# Domino_LED.net
KiCad netlist of a schematic drawn in EAGLE
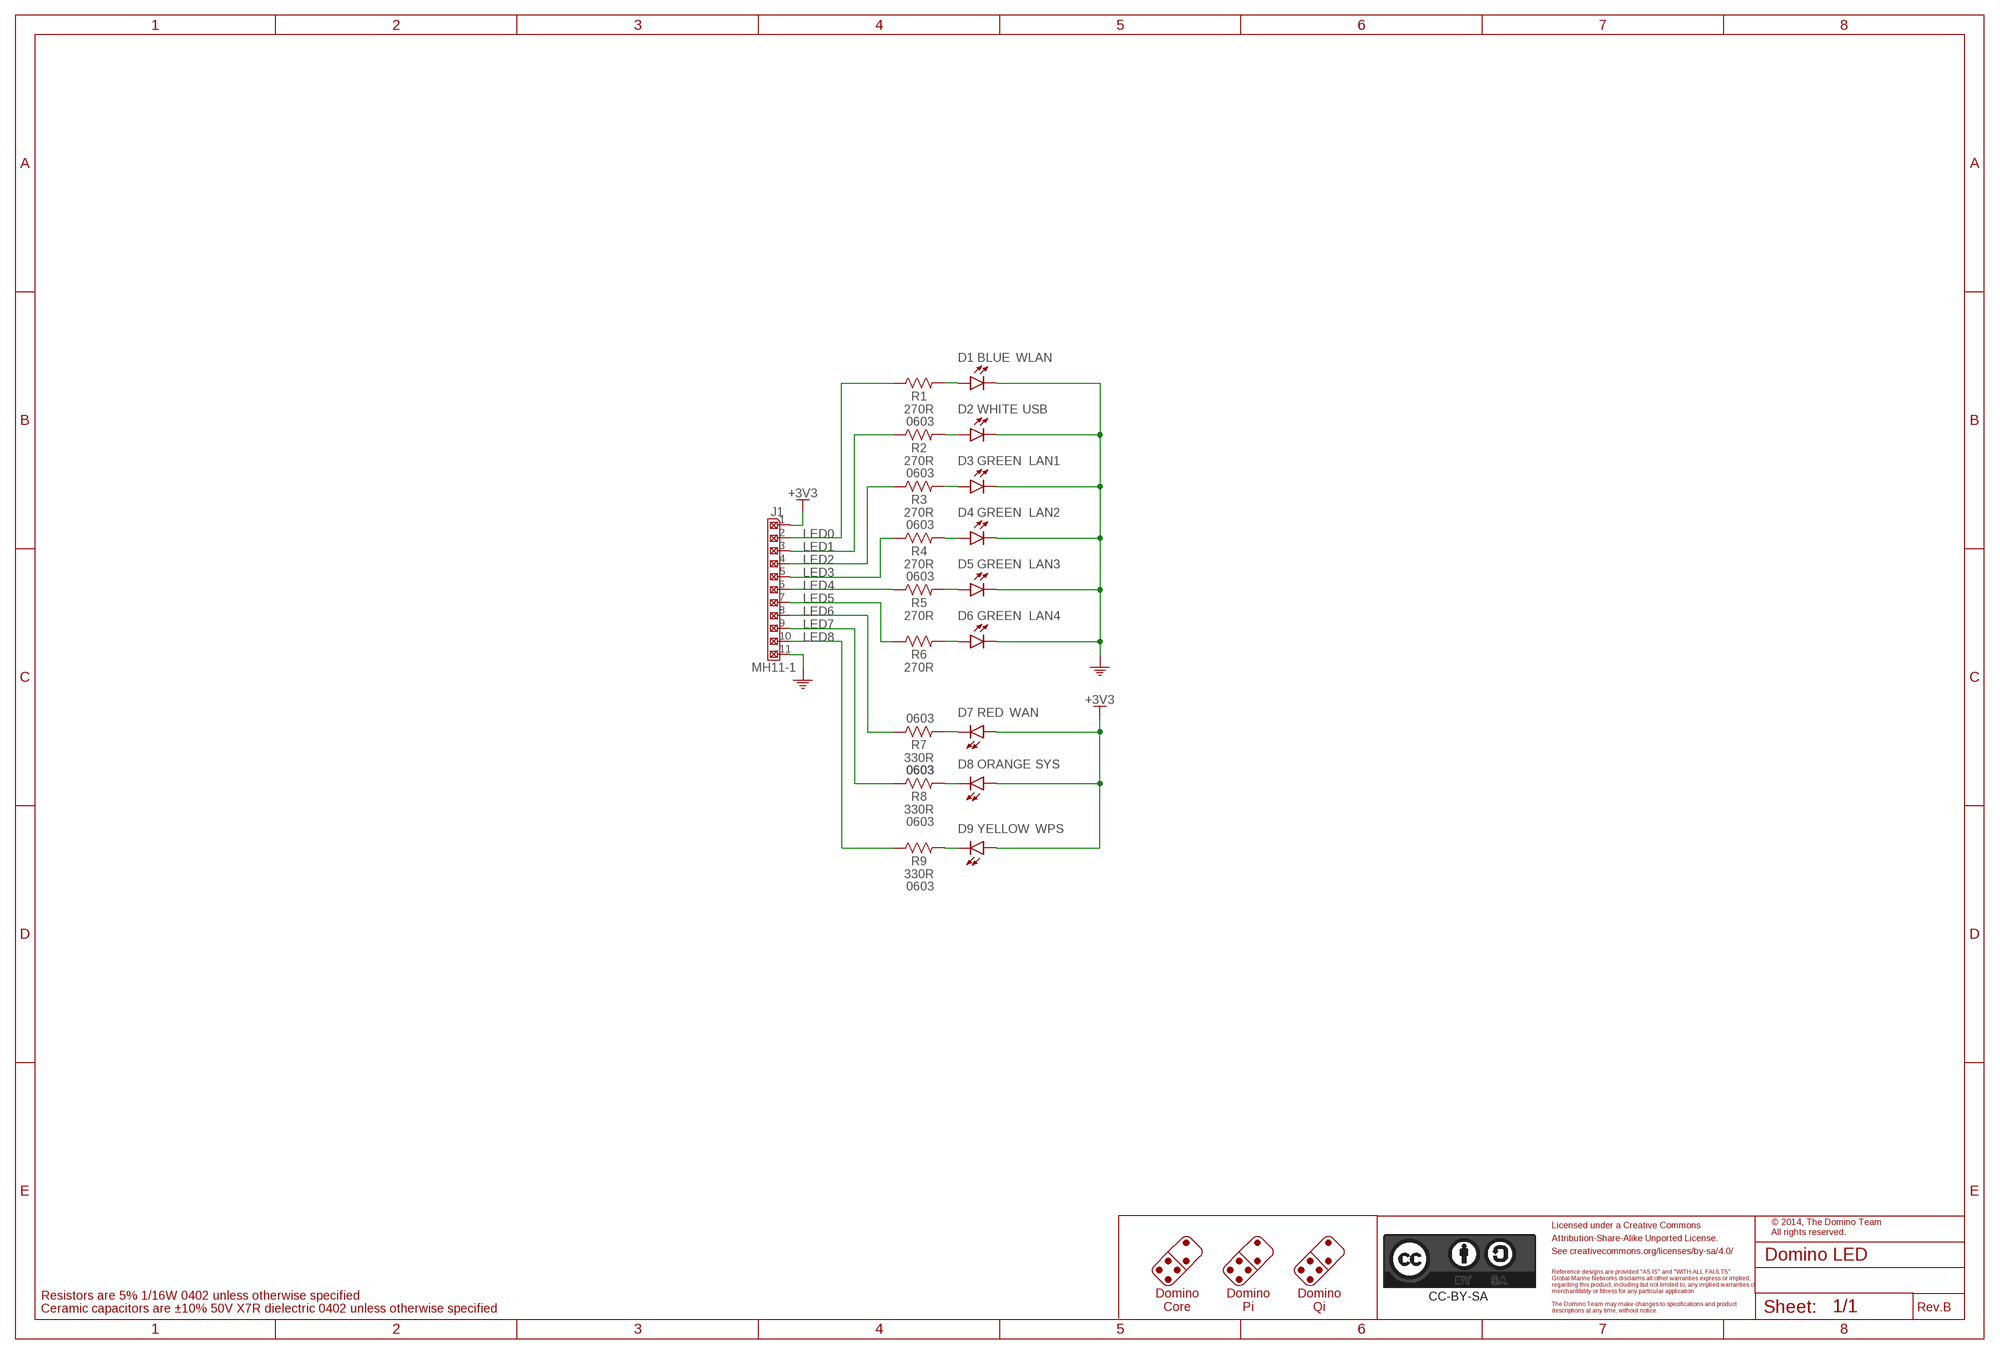
[diagram p0: schematic, sheet 1]

(export (version "E")
  (design (tool "Eeschema 10.0.6"))
  (components
    (comp (ref "CC-BY-SA1")
      (value "CC-BY-SA_LOGO")
      (footprint "eagle-import:CC-BY-SA_LOGO")
      (libsource (lib "eagle-import") (part "CC-BY-SA_LOGO"))
    )
    (comp (ref "D1")
      (value "BLUE")
      (footprint "eagle-import:LED0603")
      (fields (field (name "PARTNO") "LED0603-BLUE"))
      (libsource (lib "eagle-import") (part "LED_0603"))
    )
    (comp (ref "D2")
      (value "WHITE")
      (footprint "eagle-import:LED0603")
      (fields (field (name "PARTNO") "LED0603-WHITE"))
      (libsource (lib "eagle-import") (part "LED_0603"))
    )
    (comp (ref "D3")
      (value "GREEN")
      (footprint "eagle-import:LED0603")
      (fields (field (name "PARTNO") "LED0603-GREEN"))
      (libsource (lib "eagle-import") (part "LED_0603"))
    )
    (comp (ref "D4")
      (value "GREEN")
      (footprint "eagle-import:LED0603")
      (fields (field (name "PARTNO") "LED0603-GREEN"))
      (libsource (lib "eagle-import") (part "LED_0603"))
    )
    (comp (ref "D5")
      (value "GREEN")
      (footprint "eagle-import:LED0603")
      (fields (field (name "PARTNO") "LED0603-GREEN"))
      (libsource (lib "eagle-import") (part "LED_0603"))
    )
    (comp (ref "D6")
      (value "GREEN")
      (footprint "eagle-import:LED0603")
      (fields (field (name "PARTNO") "LED0603-GREEN"))
      (libsource (lib "eagle-import") (part "LED_0603"))
    )
    (comp (ref "D7")
      (value "RED")
      (footprint "eagle-import:LED0603")
      (fields (field (name "PARTNO") "LED0603-RED"))
      (libsource (lib "eagle-import") (part "LED_0603"))
    )
    (comp (ref "D8")
      (value "ORANGE")
      (footprint "eagle-import:LED0603")
      (fields (field (name "PARTNO") "LED0603-ORANGE"))
      (libsource (lib "eagle-import") (part "LED_0603"))
    )
    (comp (ref "D9")
      (value "YELLOW")
      (footprint "eagle-import:LED0603")
      (fields (field (name "PARTNO") "LED0603-YELLOW"))
      (libsource (lib "eagle-import") (part "LED_0603"))
    )
    (comp (ref "J1")
      (value "MH11-1")
      (footprint "eagle-import:MH11-1-0.1")
      (fields (field (name "PARTNO") "MH11-1-0.1"))
      (libsource (lib "eagle-import") (part "MH11-1"))
    )
    (comp (ref "R1")
      (value "270R")
      (footprint "eagle-import:R0603")
      (fields (field (name "SIZE") "0603") (field (name "PARTNO") "R0603_270R_5%_125mW"))
      (libsource (lib "eagle-import") (part "RES_0603"))
    )
    (comp (ref "R2")
      (value "270R")
      (footprint "eagle-import:R0603")
      (fields (field (name "SIZE") "0603") (field (name "PARTNO") "R0603_270R_5%_125mW"))
      (libsource (lib "eagle-import") (part "RES_0603"))
    )
    (comp (ref "R3")
      (value "270R")
      (footprint "eagle-import:R0603")
      (fields (field (name "SIZE") "0603") (field (name "PARTNO") "R0603_270R_5%_125mW"))
      (libsource (lib "eagle-import") (part "RES_0603"))
    )
    (comp (ref "R4")
      (value "270R")
      (footprint "eagle-import:R0603")
      (fields (field (name "SIZE") "0603") (field (name "PARTNO") "R0603_270R_5%_125mW"))
      (libsource (lib "eagle-import") (part "RES_0603"))
    )
    (comp (ref "R5")
      (value "270R")
      (footprint "eagle-import:R0603")
      (fields (field (name "SIZE") "0603") (field (name "PARTNO") "R0603_270R_5%_125mW"))
      (libsource (lib "eagle-import") (part "RES_0603"))
    )
    (comp (ref "R6")
      (value "270R")
      (footprint "eagle-import:R0603")
      (fields (field (name "SIZE") "0603") (field (name "PARTNO") "R0603_270R_5%_125mW"))
      (libsource (lib "eagle-import") (part "RES_0603"))
    )
    (comp (ref "R7")
      (value "330R")
      (footprint "eagle-import:R0603")
      (fields (field (name "SIZE") "0603") (field (name "PARTNO") "R0603_330R_5%_125mW"))
      (libsource (lib "eagle-import") (part "RES_0603"))
    )
    (comp (ref "R8")
      (value "330R")
      (footprint "eagle-import:R0603")
      (fields (field (name "SIZE") "0603") (field (name "PARTNO") "R0603_330R_5%_125mW"))
      (libsource (lib "eagle-import") (part "RES_0603"))
    )
    (comp (ref "R9")
      (value "330R")
      (footprint "eagle-import:R0603")
      (fields (field (name "SIZE") "0603") (field (name "PARTNO") "R0603_330R_5%_125mW"))
      (libsource (lib "eagle-import") (part "RES_0603"))
    )
  )
  (nets
    (net (code "1") (name "+3V3") (class "Default")
      (node (ref "D7") (pin "2") (pinfunction "A_2") (pintype "passive"))
      (node (ref "D8") (pin "2") (pinfunction "A_2") (pintype "passive"))
      (node (ref "D9") (pin "2") (pinfunction "A_2") (pintype "passive"))
      (node (ref "J1") (pin "1") (pinfunction "1_1") (pintype "passive"))
    )
    (net (code "2") (name "/LED0") (class "Default")
      (node (ref "J1") (pin "2") (pinfunction "2_2") (pintype "passive"))
      (node (ref "R1") (pin "1") (pinfunction "1_1") (pintype "passive"))
    )
    (net (code "3") (name "/LED1") (class "Default")
      (node (ref "J1") (pin "3") (pinfunction "3_3") (pintype "passive"))
      (node (ref "R2") (pin "1") (pinfunction "1_1") (pintype "passive"))
    )
    (net (code "4") (name "/LED2") (class "Default")
      (node (ref "J1") (pin "4") (pinfunction "4_4") (pintype "passive"))
      (node (ref "R3") (pin "1") (pinfunction "1_1") (pintype "passive"))
    )
    (net (code "5") (name "/LED3") (class "Default")
      (node (ref "J1") (pin "5") (pinfunction "5_5") (pintype "passive"))
      (node (ref "R4") (pin "1") (pinfunction "1_1") (pintype "passive"))
    )
    (net (code "6") (name "/LED4") (class "Default")
      (node (ref "J1") (pin "6") (pinfunction "6_6") (pintype "passive"))
      (node (ref "R5") (pin "1") (pinfunction "1_1") (pintype "passive"))
    )
    (net (code "7") (name "/LED5") (class "Default")
      (node (ref "J1") (pin "7") (pinfunction "7_7") (pintype "passive"))
      (node (ref "R6") (pin "1") (pinfunction "1_1") (pintype "passive"))
    )
    (net (code "8") (name "/LED6") (class "Default")
      (node (ref "J1") (pin "8") (pinfunction "8_8") (pintype "passive"))
      (node (ref "R7") (pin "1") (pinfunction "1_1") (pintype "passive"))
    )
    (net (code "9") (name "/LED7") (class "Default")
      (node (ref "J1") (pin "9") (pinfunction "9_9") (pintype "passive"))
      (node (ref "R8") (pin "1") (pinfunction "1_1") (pintype "passive"))
    )
    (net (code "10") (name "/LED8") (class "Default")
      (node (ref "J1") (pin "10") (pinfunction "10_10") (pintype "passive"))
      (node (ref "R9") (pin "1") (pinfunction "1_1") (pintype "passive"))
    )
    (net (code "11") (name "GND") (class "Default")
      (node (ref "D1") (pin "1") (pinfunction "C_1") (pintype "passive"))
      (node (ref "D2") (pin "1") (pinfunction "C_1") (pintype "passive"))
      (node (ref "D3") (pin "1") (pinfunction "C_1") (pintype "passive"))
      (node (ref "D4") (pin "1") (pinfunction "C_1") (pintype "passive"))
      (node (ref "D5") (pin "1") (pinfunction "C_1") (pintype "passive"))
      (node (ref "D6") (pin "1") (pinfunction "C_1") (pintype "passive"))
      (node (ref "J1") (pin "11") (pinfunction "11_11") (pintype "passive"))
    )
    (net (code "12") (name "Net-(D1-A)") (class "Default")
      (node (ref "D1") (pin "2") (pinfunction "A_2") (pintype "passive"))
      (node (ref "R1") (pin "2") (pinfunction "2_2") (pintype "passive"))
    )
    (net (code "13") (name "Net-(D2-A)") (class "Default")
      (node (ref "D2") (pin "2") (pinfunction "A_2") (pintype "passive"))
      (node (ref "R2") (pin "2") (pinfunction "2_2") (pintype "passive"))
    )
    (net (code "14") (name "Net-(D3-A)") (class "Default")
      (node (ref "D3") (pin "2") (pinfunction "A_2") (pintype "passive"))
      (node (ref "R3") (pin "2") (pinfunction "2_2") (pintype "passive"))
    )
    (net (code "15") (name "Net-(D4-A)") (class "Default")
      (node (ref "D4") (pin "2") (pinfunction "A_2") (pintype "passive"))
      (node (ref "R4") (pin "2") (pinfunction "2_2") (pintype "passive"))
    )
    (net (code "16") (name "Net-(D5-A)") (class "Default")
      (node (ref "D5") (pin "2") (pinfunction "A_2") (pintype "passive"))
      (node (ref "R5") (pin "2") (pinfunction "2_2") (pintype "passive"))
    )
    (net (code "17") (name "Net-(D6-A)") (class "Default")
      (node (ref "D6") (pin "2") (pinfunction "A_2") (pintype "passive"))
      (node (ref "R6") (pin "2") (pinfunction "2_2") (pintype "passive"))
    )
    (net (code "18") (name "Net-(D7-C)") (class "Default")
      (node (ref "D7") (pin "1") (pinfunction "C_1") (pintype "passive"))
      (node (ref "R7") (pin "2") (pinfunction "2_2") (pintype "passive"))
    )
    (net (code "19") (name "Net-(D8-C)") (class "Default")
      (node (ref "D8") (pin "1") (pinfunction "C_1") (pintype "passive"))
      (node (ref "R8") (pin "2") (pinfunction "2_2") (pintype "passive"))
    )
    (net (code "20") (name "Net-(D9-C)") (class "Default")
      (node (ref "D9") (pin "1") (pinfunction "C_1") (pintype "passive"))
      (node (ref "R9") (pin "2") (pinfunction "2_2") (pintype "passive"))
    )
  )
)
